# RS485_main.net
KiCad netlist of a schematic drawn in Altium Designer
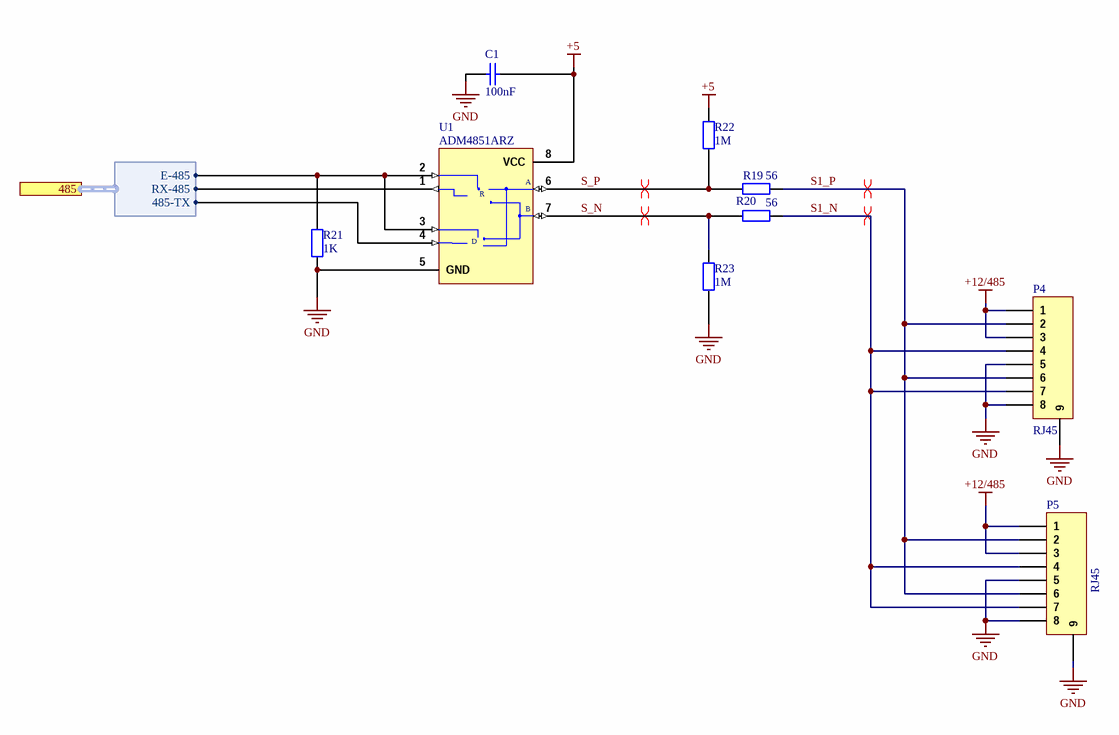
[diagram p0: RS485 main.SchDoc]

(export (version "E")
  (design (tool "Eeschema 10.0.6"))
  (components
    (comp (ref "C1")
      (value "100nF")
      (footprint "C0805")
      (description "Capacitor")
      (fields
        (field (name "MANUFACTURER") "MULTICOMP")
        (field (name "MANUFACTURER PART NUMBER") "MCCA000296")
      )
      (libsource (lib "BRA") (part "Cap 0805 100nF"))
    )
    (comp (ref "P4")
      (value "RJ45")
      (footprint "MOLEX-RJ45_855135013")
      (description "Header, 8-Pin")
      (fields
        (field (name "MANUFACTURER") "MOLEX")
        (field (name "MANUFACTURER PART NUMBER") "85513-5013")
        (field (name "APPROVAL CATEGORY") "UL 94V-0")
        (field (name "LONGUEUR/HAUTEUR") "13")
      )
      (libsource (lib "MAIN BOARD CERES") (part "Header 8"))
    )
    (comp (ref "P5")
      (value "RJ45")
      (footprint "MOLEX-RJ45_855135013")
      (description "Header, 8-Pin")
      (fields
        (field (name "MANUFACTURER") "MOLEX")
        (field (name "MANUFACTURER PART NUMBER") "85513-5013")
        (field (name "APPROVAL CATEGORY") "UL 94V-0")
        (field (name "LONGUEUR/HAUTEUR") "13")
      )
      (libsource (lib "MAIN BOARD CERES") (part "Header 8"))
    )
    (comp (ref "R19")
      (value "56")
      (footprint "R0805")
      (description "Resistor")
      (fields
        (field (name "MANUFACTURER") "MULTICOMP")
        (field (name "MANUFACTURER PART NUMBER") "MC01W0805156R")
      )
      (libsource (lib "BRA") (part "Resistor 0805 56"))
    )
    (comp (ref "R20")
      (value "56")
      (footprint "R0805")
      (description "Resistor")
      (fields
        (field (name "MANUFACTURER") "MULTICOMP")
        (field (name "MANUFACTURER PART NUMBER") "MC01W0805156R")
      )
      (libsource (lib "BRA") (part "Resistor 0805 56"))
    )
    (comp (ref "R21")
      (value "1K")
      (footprint "R0805")
      (description "Resistor")
      (fields
        (field (name "MANUFACTURER") "MULTICOMP")
        (field (name "MANUFACTURER PART NUMBER") "MC0.1W08051%1KFR")
      )
      (libsource (lib "BRA") (part "Resistor 0805 1K"))
    )
    (comp (ref "R22")
      (value "1M")
      (footprint "R0805")
      (description "Resistor")
      (fields
        (field (name "MANUFACTURER") "MULTICOMP")
        (field (name "MANUFACTURER PART NUMBER") "MC01W080511M")
      )
      (libsource (lib "BRA") (part "Resistor 0805 680"))
    )
    (comp (ref "R23")
      (value "1M")
      (footprint "R0805")
      (description "Resistor")
      (fields
        (field (name "MANUFACTURER") "MULTICOMP")
        (field (name "MANUFACTURER PART NUMBER") "MC01W080511M")
      )
      (libsource (lib "BRA") (part "Resistor 0805 680"))
    )
    (comp (ref "U1")
      (value "ADM4851ARZ")
      (footprint "SOIC8")
      (description "Low-Power, Slew-Rate-Limited RS-485/RS-422 Transceiver")
      (fields (field (name "MANUFACTURER") "ANALOG DEVICES"))
      (libsource (lib "Maxim Communication Transceiver") (part "MAX485ESA"))
    )
  )
  (nets
    (net (code "2") (name "+5") (class "Default")
      (node (ref "C1") (pin "1") (pinfunction "1_1") (pintype "passive"))
      (node (ref "R22") (pin "2") (pinfunction "2_2") (pintype "passive"))
      (node (ref "U1") (pin "8") (pinfunction "VCC_8") (pintype "power_in"))
    )
    (net (code "3") (name "+12{slash}485") (class "Default")
      (node (ref "P4") (pin "1") (pinfunction "1_1") (pintype "passive"))
      (node (ref "P4") (pin "3") (pinfunction "3_3") (pintype "passive"))
      (node (ref "P5") (pin "1") (pinfunction "1_1") (pintype "passive"))
      (node (ref "P5") (pin "3") (pinfunction "3_3") (pintype "passive"))
    )
    (net (code "4") (name "/485-TX") (class "Default")
      (node (ref "U1") (pin "4") (pinfunction "DI_4") (pintype "input"))
    )
    (net (code "5") (name "/E-485") (class "Default")
      (node (ref "R21") (pin "2") (pinfunction "2_2") (pintype "passive"))
      (node (ref "U1") (pin "2") (pinfunction "~{RE}_2") (pintype "input"))
      (node (ref "U1") (pin "3") (pinfunction "DE_3") (pintype "input"))
    )
    (net (code "6") (name "/RX-485") (class "Default")
      (node (ref "U1") (pin "1") (pinfunction "RO_1") (pintype "output"))
    )
    (net (code "7") (name "/S1_N") (class "Default")
      (node (ref "P4") (pin "4") (pinfunction "4_4") (pintype "passive"))
      (node (ref "P4") (pin "7") (pinfunction "7_7") (pintype "passive"))
      (node (ref "P5") (pin "4") (pinfunction "4_4") (pintype "passive"))
      (node (ref "P5") (pin "7") (pinfunction "7_7") (pintype "passive"))
      (node (ref "R20") (pin "2") (pinfunction "2_2") (pintype "passive"))
    )
    (net (code "8") (name "/S1_P") (class "Default")
      (node (ref "P4") (pin "2") (pinfunction "2_2") (pintype "passive"))
      (node (ref "P4") (pin "6") (pinfunction "6_6") (pintype "passive"))
      (node (ref "P5") (pin "2") (pinfunction "2_2") (pintype "passive"))
      (node (ref "P5") (pin "6") (pinfunction "6_6") (pintype "passive"))
      (node (ref "R19") (pin "2") (pinfunction "2_2") (pintype "passive"))
    )
    (net (code "9") (name "/S_N") (class "Default")
      (node (ref "R20") (pin "1") (pinfunction "1_1") (pintype "passive"))
      (node (ref "R23") (pin "2") (pinfunction "2_2") (pintype "passive"))
      (node (ref "U1") (pin "7") (pinfunction "B_7") (pintype "bidirectional"))
    )
    (net (code "10") (name "/S_P") (class "Default")
      (node (ref "R19") (pin "1") (pinfunction "1_1") (pintype "passive"))
      (node (ref "R22") (pin "1") (pinfunction "1_1") (pintype "passive"))
      (node (ref "U1") (pin "6") (pinfunction "A_6") (pintype "bidirectional"))
    )
    (net (code "12") (name "GND") (class "Default")
      (node (ref "C1") (pin "2") (pinfunction "2_2") (pintype "passive"))
      (node (ref "P4") (pin "5") (pinfunction "5_5") (pintype "passive"))
      (node (ref "P4") (pin "8") (pinfunction "8_8") (pintype "passive"))
      (node (ref "P4") (pin "9") (pinfunction "9_9") (pintype "passive"))
      (node (ref "P5") (pin "5") (pinfunction "5_5") (pintype "passive"))
      (node (ref "P5") (pin "8") (pinfunction "8_8") (pintype "passive"))
      (node (ref "P5") (pin "9") (pinfunction "9_9") (pintype "passive"))
      (node (ref "R21") (pin "1") (pinfunction "1_1") (pintype "passive"))
      (node (ref "R23") (pin "1") (pinfunction "1_1") (pintype "passive"))
      (node (ref "U1") (pin "5") (pinfunction "GND_5") (pintype "power_in"))
    )
  )
)
